# avr_saber_mini.net
KiCad netlist of a schematic drawn in EAGLE
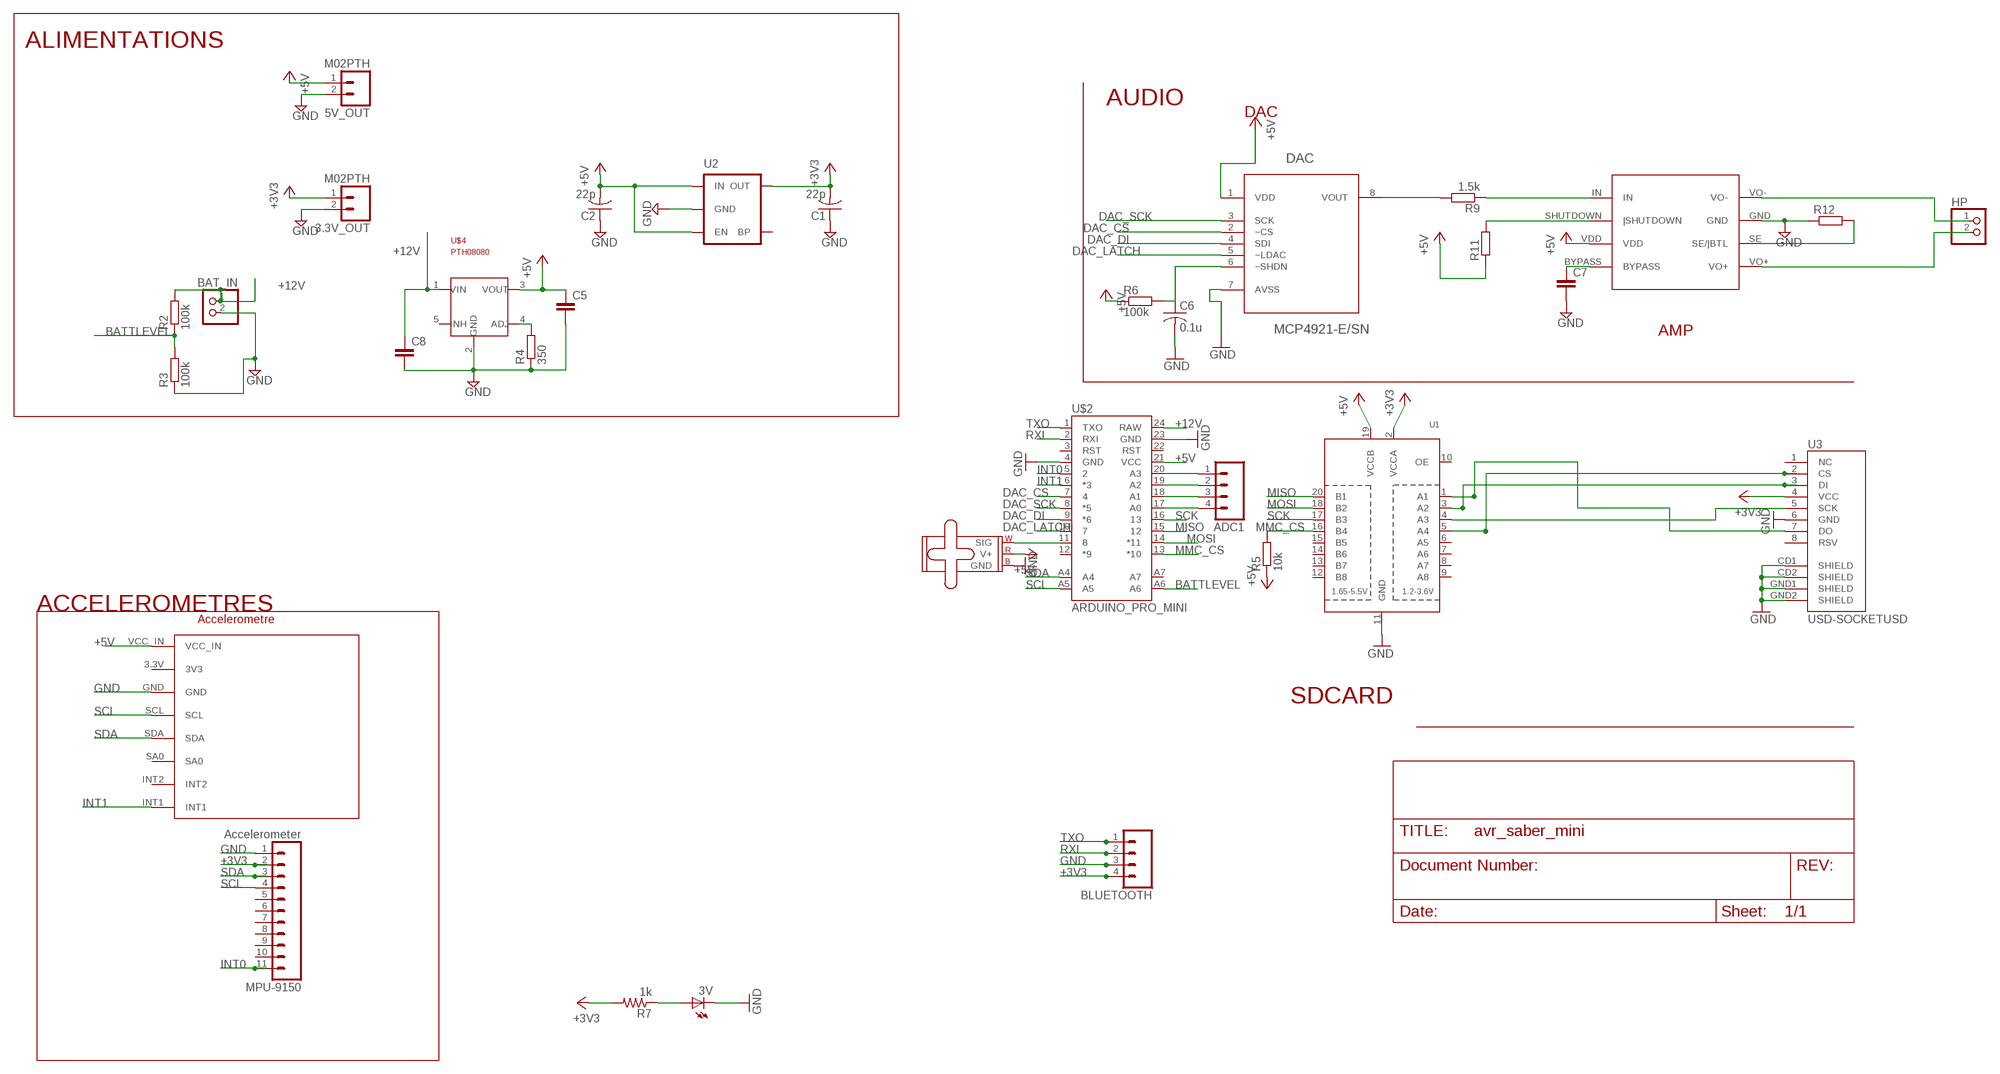
[diagram p0: schematic, sheet 1]

(export (version "E")
  (design (tool "Eeschema 10.0.6"))
  (components
    (comp (ref "3.3V_OUT")
      (value "M02PTH")
      (footprint "eagle-import:1X02")
      (libsource (lib "eagle-import") (part "M02PTH"))
    )
    (comp (ref "3V")
      (value "LEDSML0805")
      (footprint "eagle-import:SML0805")
      (libsource (lib "eagle-import") (part "LEDSML0805"))
    )
    (comp (ref "5V_OUT")
      (value "M02PTH")
      (footprint "eagle-import:1X02")
      (libsource (lib "eagle-import") (part "M02PTH"))
    )
    (comp (ref "ADC1")
      (value "M04PTH")
      (footprint "eagle-import:1X04")
      (libsource (lib "eagle-import") (part "M04PTH"))
    )
    (comp (ref "BAT_IN")
      (value "PINHD-1X2")
      (footprint "eagle-import:1X02")
      (libsource (lib "eagle-import") (part "PINHD-1X2"))
    )
    (comp (ref "BLUETOOTH")
      (value "M04PTH")
      (footprint "eagle-import:1X04")
      (libsource (lib "eagle-import") (part "M04PTH"))
    )
    (comp (ref "C1")
      (value "22p")
      (footprint "eagle-import:C0805")
      (libsource (lib "eagle-import") (part "C-USC0805"))
    )
    (comp (ref "C2")
      (value "22p")
      (footprint "eagle-import:C0805")
      (libsource (lib "eagle-import") (part "C-USC0805"))
    )
    (comp (ref "C5")
      (value "C-EUC1206K")
      (footprint "eagle-import:C1206K")
      (libsource (lib "eagle-import") (part "C-EUC1206K"))
    )
    (comp (ref "C6")
      (value "0.1u")
      (footprint "eagle-import:C0805")
      (libsource (lib "eagle-import") (part "C-USC0805"))
    )
    (comp (ref "C7")
      (value "C-EU025-025X050")
      (footprint "eagle-import:C025-025X050")
      (libsource (lib "eagle-import") (part "C-EU025-025X050"))
    )
    (comp (ref "C8")
      (value "C-EUC1206K")
      (footprint "eagle-import:C1206K")
      (libsource (lib "eagle-import") (part "C-EUC1206K"))
    )
    (comp (ref "DAC")
      (value "MCP4921-E/SN")
      (footprint "eagle-import:SOIC8-N_MC")
      (libsource (lib "eagle-import") (part "MCP4921-E/SN"))
    )
    (comp (ref "HP")
      (value "PINHD-1X2")
      (footprint "eagle-import:1X02")
      (libsource (lib "eagle-import") (part "PINHD-1X2"))
    )
    (comp (ref "LED1")
      (value "SMALL_SERVO")
      (footprint "eagle-import:1X03")
      (libsource (lib "eagle-import") (part "SMALL_SERVO"))
    )
    (comp (ref "MMA8451")
      (value "DEV")
      (footprint "eagle-import:MMA8451")
      (libsource (lib "eagle-import") (part "DEV"))
    )
    (comp (ref "MPU-9150")
      (value "Accelerometer")
      (footprint "eagle-import:1X11")
      (libsource (lib "eagle-import") (part "M11PTH"))
    )
    (comp (ref "R2")
      (value "100k")
      (footprint "eagle-import:R0805")
      (libsource (lib "eagle-import") (part "R-EU_R0805"))
    )
    (comp (ref "R3")
      (value "100k")
      (footprint "eagle-import:R0805")
      (libsource (lib "eagle-import") (part "R-EU_R0805"))
    )
    (comp (ref "R4")
      (value "350")
      (footprint "eagle-import:R0805")
      (libsource (lib "eagle-import") (part "R-EU_R0805"))
    )
    (comp (ref "R5")
      (value "10k")
      (footprint "eagle-import:R0805")
      (libsource (lib "eagle-import") (part "R-EU_R0805"))
    )
    (comp (ref "R6")
      (value "100k")
      (footprint "eagle-import:R0805")
      (libsource (lib "eagle-import") (part "R-EU_R0805"))
    )
    (comp (ref "R7")
      (value "1k")
      (footprint "eagle-import:M0805")
      (libsource (lib "eagle-import") (part "R-US_M0805"))
    )
    (comp (ref "R9")
      (value "1.5k")
      (footprint "eagle-import:R0805")
      (libsource (lib "eagle-import") (part "R-EU_R0805"))
    )
    (comp (ref "R11")
      (value "R-EU_R0805")
      (footprint "eagle-import:R0805")
      (libsource (lib "eagle-import") (part "R-EU_R0805"))
    )
    (comp (ref "R12")
      (value "R-EU_R0805")
      (footprint "eagle-import:R0805")
      (libsource (lib "eagle-import") (part "R-EU_R0805"))
    )
    (comp (ref "U$1")
      (value "TPA0211")
      (footprint "eagle-import:TPA0211")
      (libsource (lib "eagle-import") (part "TPA0211"))
    )
    (comp (ref "U$2")
      (value "ARDUINO_PRO_MINI")
      (footprint "eagle-import:ARDUINO_PRO_MINI")
      (libsource (lib "eagle-import") (part "ARDUINO_PRO_MINI"))
    )
    (comp (ref "U$4")
      (value "PTH08080")
      (footprint "eagle-import:PTH08080EUF")
      (libsource (lib "eagle-import") (part "PTH08080"))
    )
    (comp (ref "U1")
      (value "TXB0108PWR")
      (footprint "eagle-import:TSSOP20")
      (libsource (lib "eagle-import") (part "TXB0108PWR"))
    )
    (comp (ref "U2")
      (value "MIC52053.3V")
      (footprint "eagle-import:SOT23-5")
      (libsource (lib "eagle-import") (part "MIC52053.3V"))
    )
    (comp (ref "U3")
      (value "USD-SOCKETUSD")
      (footprint "eagle-import:USD-SOCKET-PP")
      (libsource (lib "eagle-import") (part "USD-SOCKETUSD"))
    )
  )
  (nets
    (net (code "1") (name "+3V3") (class "Default")
      (node (ref "3.3V_OUT") (pin "1") (pinfunction "1_1") (pintype "passive"))
      (node (ref "BLUETOOTH") (pin "4") (pinfunction "4_4") (pintype "passive"))
      (node (ref "C1") (pin "2") (pinfunction "2_2") (pintype "passive"))
      (node (ref "MPU-9150") (pin "2") (pinfunction "2_2") (pintype "passive"))
      (node (ref "R7") (pin "2") (pinfunction "2_2") (pintype "passive"))
      (node (ref "U1") (pin "2") (pinfunction "VCCA_2") (pintype "bidirectional"))
      (node (ref "U2") (pin "5") (pinfunction "OUT_5") (pintype "passive"))
      (node (ref "U3") (pin "4") (pinfunction "VCC_4") (pintype "bidirectional"))
    )
    (net (code "2") (name "+5V") (class "Default")
      (node (ref "5V_OUT") (pin "1") (pinfunction "1_1") (pintype "passive"))
      (node (ref "C2") (pin "2") (pinfunction "2_2") (pintype "passive"))
      (node (ref "C5") (pin "1") (pinfunction "1_1") (pintype "passive"))
      (node (ref "DAC") (pin "1") (pinfunction "VDD_1") (pintype "power_in"))
      (node (ref "LED1") (pin "2") (pinfunction "V+_2") (pintype "bidirectional"))
      (node (ref "MMA8451") (pin "VCC_IN") (pinfunction "VCC_IN_VCC_IN") (pintype "bidirectional"))
      (node (ref "R11") (pin "1") (pinfunction "1_1") (pintype "passive"))
      (node (ref "R5") (pin "1") (pinfunction "1_1") (pintype "passive"))
      (node (ref "R6") (pin "1") (pinfunction "1_1") (pintype "passive"))
      (node (ref "U$1") (pin "VDD") (pinfunction "VDD_VDD") (pintype "bidirectional"))
      (node (ref "U$2") (pin "21") (pinfunction "VCC_21") (pintype "bidirectional"))
      (node (ref "U$4") (pin "3") (pinfunction "VOUT_3") (pintype "power_in"))
      (node (ref "U1") (pin "19") (pinfunction "VCCB_19") (pintype "bidirectional"))
      (node (ref "U2") (pin "1") (pinfunction "IN_1") (pintype "input"))
      (node (ref "U2") (pin "3") (pinfunction "EN_3") (pintype "input"))
    )
    (net (code "3") (name "/+12V") (class "Default")
      (node (ref "BAT_IN") (pin "1") (pinfunction "1_1") (pintype "passive"))
      (node (ref "C8") (pin "1") (pinfunction "1_1") (pintype "passive"))
      (node (ref "R2") (pin "2") (pinfunction "2_2") (pintype "passive"))
      (node (ref "U$2") (pin "24") (pinfunction "RAW_24") (pintype "bidirectional"))
      (node (ref "U$4") (pin "1") (pinfunction "VIN_1") (pintype "power_in"))
    )
    (net (code "4") (name "/BATTLEVEL") (class "Default")
      (node (ref "R2") (pin "1") (pinfunction "1_1") (pintype "passive"))
      (node (ref "R3") (pin "2") (pinfunction "2_2") (pintype "passive"))
      (node (ref "U$2") (pin "A6") (pinfunction "A6_A6") (pintype "bidirectional"))
    )
    (net (code "5") (name "/DAC_CS") (class "Default")
      (node (ref "DAC") (pin "2") (pinfunction "~{CS}_2") (pintype "input"))
      (node (ref "U$2") (pin "7") (pinfunction "4_7") (pintype "bidirectional"))
    )
    (net (code "6") (name "/DAC_DI") (class "Default")
      (node (ref "DAC") (pin "4") (pinfunction "SDI_4") (pintype "input"))
      (node (ref "U$2") (pin "9") (pinfunction "*6_9") (pintype "bidirectional"))
    )
    (net (code "7") (name "/DAC_LATCH") (class "Default")
      (node (ref "DAC") (pin "5") (pinfunction "~{LDAC}_5") (pintype "input"))
      (node (ref "U$2") (pin "10") (pinfunction "7_10") (pintype "bidirectional"))
    )
    (net (code "8") (name "/DAC_SCK") (class "Default")
      (node (ref "DAC") (pin "3") (pinfunction "SCK_3") (pintype "input"))
      (node (ref "U$2") (pin "8") (pinfunction "*5_8") (pintype "bidirectional"))
    )
    (net (code "9") (name "/INT0") (class "Default")
      (node (ref "MPU-9150") (pin "11") (pinfunction "11_11") (pintype "passive"))
      (node (ref "U$2") (pin "5") (pinfunction "2_5") (pintype "bidirectional"))
    )
    (net (code "10") (name "/INT1") (class "Default")
      (node (ref "MMA8451") (pin "INT1") (pinfunction "INT1_INT1") (pintype "bidirectional"))
      (node (ref "U$2") (pin "6") (pinfunction "*3_6") (pintype "bidirectional"))
    )
    (net (code "11") (name "/MISO") (class "Default")
      (node (ref "U$2") (pin "15") (pinfunction "12_15") (pintype "bidirectional"))
      (node (ref "U1") (pin "20") (pinfunction "B1_20") (pintype "bidirectional"))
    )
    (net (code "12") (name "/MMC_CS") (class "Default")
      (node (ref "R5") (pin "2") (pinfunction "2_2") (pintype "passive"))
      (node (ref "U$2") (pin "13") (pinfunction "*10_13") (pintype "bidirectional"))
      (node (ref "U1") (pin "16") (pinfunction "B4_16") (pintype "bidirectional"))
    )
    (net (code "13") (name "/MOSI") (class "Default")
      (node (ref "U$2") (pin "14") (pinfunction "*11_14") (pintype "bidirectional"))
      (node (ref "U1") (pin "18") (pinfunction "B2_18") (pintype "bidirectional"))
    )
    (net (code "14") (name "/RXI") (class "Default")
      (node (ref "BLUETOOTH") (pin "2") (pinfunction "2_2") (pintype "passive"))
      (node (ref "U$2") (pin "2") (pinfunction "RXI_2") (pintype "bidirectional"))
    )
    (net (code "15") (name "/SCK") (class "Default")
      (node (ref "U$2") (pin "16") (pinfunction "13_16") (pintype "bidirectional"))
      (node (ref "U1") (pin "17") (pinfunction "B3_17") (pintype "bidirectional"))
    )
    (net (code "16") (name "/SCL") (class "Default")
      (node (ref "MMA8451") (pin "SCL") (pinfunction "SCL_SCL") (pintype "bidirectional"))
      (node (ref "MPU-9150") (pin "4") (pinfunction "4_4") (pintype "passive"))
      (node (ref "U$2") (pin "A5") (pinfunction "A5_A5") (pintype "bidirectional"))
    )
    (net (code "17") (name "/SDA") (class "Default")
      (node (ref "MMA8451") (pin "SDA") (pinfunction "SDA_SDA") (pintype "bidirectional"))
      (node (ref "MPU-9150") (pin "3") (pinfunction "3_3") (pintype "passive"))
      (node (ref "U$2") (pin "A4") (pinfunction "A4_A4") (pintype "bidirectional"))
    )
    (net (code "18") (name "/TXO") (class "Default")
      (node (ref "BLUETOOTH") (pin "1") (pinfunction "1_1") (pintype "passive"))
      (node (ref "U$2") (pin "1") (pinfunction "TXO_1") (pintype "bidirectional"))
    )
    (net (code "19") (name "GND") (class "Default")
      (node (ref "3.3V_OUT") (pin "2") (pinfunction "2_2") (pintype "passive"))
      (node (ref "3V") (pin "C") (pinfunction "C_C") (pintype "passive"))
      (node (ref "5V_OUT") (pin "2") (pinfunction "2_2") (pintype "passive"))
      (node (ref "BAT_IN") (pin "2") (pinfunction "2_2") (pintype "passive"))
      (node (ref "BLUETOOTH") (pin "3") (pinfunction "3_3") (pintype "passive"))
      (node (ref "C1") (pin "1") (pinfunction "1_1") (pintype "passive"))
      (node (ref "C2") (pin "1") (pinfunction "1_1") (pintype "passive"))
      (node (ref "C5") (pin "2") (pinfunction "2_2") (pintype "passive"))
      (node (ref "C6") (pin "2") (pinfunction "2_2") (pintype "passive"))
      (node (ref "C7") (pin "2") (pinfunction "2_2") (pintype "passive"))
      (node (ref "C8") (pin "2") (pinfunction "2_2") (pintype "passive"))
      (node (ref "DAC") (pin "7") (pinfunction "AVSS_7") (pintype "power_in"))
      (node (ref "LED1") (pin "3") (pinfunction "GND_3") (pintype "bidirectional"))
      (node (ref "MMA8451") (pin "GND") (pinfunction "GND_GND") (pintype "bidirectional"))
      (node (ref "MPU-9150") (pin "1") (pinfunction "1_1") (pintype "passive"))
      (node (ref "R12") (pin "1") (pinfunction "1_1") (pintype "passive"))
      (node (ref "R3") (pin "1") (pinfunction "1_1") (pintype "passive"))
      (node (ref "R4") (pin "1") (pinfunction "1_1") (pintype "passive"))
      (node (ref "U$1") (pin "GND") (pinfunction "GND_GND") (pintype "bidirectional"))
      (node (ref "U$2") (pin "23") (pinfunction "GND_23") (pintype "bidirectional"))
      (node (ref "U$2") (pin "4") (pinfunction "GND_4") (pintype "bidirectional"))
      (node (ref "U$4") (pin "2") (pinfunction "GND_2") (pintype "power_in"))
      (node (ref "U1") (pin "11") (pinfunction "GND_11") (pintype "bidirectional"))
      (node (ref "U2") (pin "2") (pinfunction "GND_2") (pintype "input"))
      (node (ref "U3") (pin "6") (pinfunction "GND_6") (pintype "bidirectional"))
      (node (ref "U3") (pin "CD1") (pinfunction "SHIELD_CD1") (pintype "bidirectional"))
      (node (ref "U3") (pin "CD2") (pinfunction "SHIELD_CD2") (pintype "bidirectional"))
      (node (ref "U3") (pin "GND1") (pinfunction "SHIELD_GND1") (pintype "bidirectional"))
      (node (ref "U3") (pin "GND2") (pinfunction "SHIELD_GND2") (pintype "bidirectional"))
    )
    (net (code "20") (name "Net-(3V-PadA)") (class "Default")
      (node (ref "3V") (pin "A") (pinfunction "A_A") (pintype "passive"))
      (node (ref "R7") (pin "1") (pinfunction "1_1") (pintype "passive"))
    )
    (net (code "21") (name "Net-(C7-Pad1)") (class "Default")
      (node (ref "C7") (pin "1") (pinfunction "1_1") (pintype "passive"))
      (node (ref "U$1") (pin "BYPASS") (pinfunction "BYPASS_BYPASS") (pintype "bidirectional"))
    )
    (net (code "22") (name "Net-(DAC-VOUT)") (class "Default")
      (node (ref "DAC") (pin "8") (pinfunction "VOUT_8") (pintype "output"))
      (node (ref "R9") (pin "2") (pinfunction "2_2") (pintype "passive"))
    )
    (net (code "23") (name "Net-(DAC-~{SHDN})") (class "Default")
      (node (ref "C6") (pin "1") (pinfunction "1_1") (pintype "passive"))
      (node (ref "DAC") (pin "6") (pinfunction "~{SHDN}_6") (pintype "input"))
      (node (ref "R6") (pin "2") (pinfunction "2_2") (pintype "passive"))
    )
    (net (code "24") (name "Net-(HP-Pad1)") (class "Default")
      (node (ref "HP") (pin "1") (pinfunction "1_1") (pintype "passive"))
      (node (ref "U$1") (pin "VO-") (pinfunction "VO-_VO-") (pintype "bidirectional"))
    )
    (net (code "25") (name "Net-(HP-Pad2)") (class "Default")
      (node (ref "HP") (pin "2") (pinfunction "2_2") (pintype "passive"))
      (node (ref "U$1") (pin "VO+") (pinfunction "VO+_VO+") (pintype "bidirectional"))
    )
    (net (code "26") (name "Net-(LED1-SIG)") (class "Default")
      (node (ref "LED1") (pin "1") (pinfunction "SIG_1") (pintype "bidirectional"))
      (node (ref "U$2") (pin "11") (pinfunction "8_11") (pintype "bidirectional"))
    )
    (net (code "27") (name "Net-(R9-Pad1)") (class "Default")
      (node (ref "R9") (pin "1") (pinfunction "1_1") (pintype "passive"))
      (node (ref "U$1") (pin "IN") (pinfunction "IN_IN") (pintype "bidirectional"))
    )
    (net (code "28") (name "Net-(U$1-SE{slash}|BTL)") (class "Default")
      (node (ref "R12") (pin "2") (pinfunction "2_2") (pintype "passive"))
      (node (ref "U$1") (pin "SE") (pinfunction "SE/|BTL_SE") (pintype "bidirectional"))
    )
    (net (code "29") (name "Net-(U$1-|SHUTDOWN)") (class "Default")
      (node (ref "R11") (pin "2") (pinfunction "2_2") (pintype "passive"))
      (node (ref "U$1") (pin "SHUTDOWN") (pinfunction "|SHUTDOWN_SHUTDOWN") (pintype "bidirectional"))
    )
    (net (code "30") (name "Net-(U$2-A0)") (class "Default")
      (node (ref "ADC1") (pin "4") (pinfunction "4_4") (pintype "passive"))
      (node (ref "U$2") (pin "17") (pinfunction "A0_17") (pintype "bidirectional"))
    )
    (net (code "31") (name "Net-(U$2-A1)") (class "Default")
      (node (ref "ADC1") (pin "3") (pinfunction "3_3") (pintype "passive"))
      (node (ref "U$2") (pin "18") (pinfunction "A1_18") (pintype "bidirectional"))
    )
    (net (code "32") (name "Net-(U$2-A2)") (class "Default")
      (node (ref "ADC1") (pin "2") (pinfunction "2_2") (pintype "passive"))
      (node (ref "U$2") (pin "19") (pinfunction "A2_19") (pintype "bidirectional"))
    )
    (net (code "33") (name "Net-(U$2-A3)") (class "Default")
      (node (ref "ADC1") (pin "1") (pinfunction "1_1") (pintype "passive"))
      (node (ref "U$2") (pin "20") (pinfunction "A3_20") (pintype "bidirectional"))
    )
    (net (code "34") (name "Net-(U$4-ADJ)") (class "Default")
      (node (ref "R4") (pin "2") (pinfunction "2_2") (pintype "passive"))
      (node (ref "U$4") (pin "4") (pinfunction "ADJ_4") (pintype "passive"))
    )
    (net (code "35") (name "Net-(U1-A1)") (class "Default")
      (node (ref "U1") (pin "1") (pinfunction "A1_1") (pintype "bidirectional"))
      (node (ref "U3") (pin "7") (pinfunction "DO_7") (pintype "bidirectional"))
    )
    (net (code "36") (name "Net-(U1-A2)") (class "Default")
      (node (ref "U1") (pin "3") (pinfunction "A2_3") (pintype "bidirectional"))
      (node (ref "U3") (pin "3") (pinfunction "DI_3") (pintype "bidirectional"))
    )
    (net (code "37") (name "Net-(U1-A3)") (class "Default")
      (node (ref "U1") (pin "4") (pinfunction "A3_4") (pintype "bidirectional"))
      (node (ref "U3") (pin "5") (pinfunction "SCK_5") (pintype "bidirectional"))
    )
    (net (code "38") (name "Net-(U1-A4)") (class "Default")
      (node (ref "U1") (pin "5") (pinfunction "A4_5") (pintype "bidirectional"))
      (node (ref "U3") (pin "2") (pinfunction "CS_2") (pintype "bidirectional"))
    )
    (net (code "39") (name "unconnected-(MMA8451-3V3-Pad3.3V)") (class "Default")
      (node (ref "MMA8451") (pin "3.3V") (pinfunction "3V3_3.3V") (pintype "bidirectional"))
    )
    (net (code "40") (name "unconnected-(MMA8451-PadINT2)") (class "Default")
      (node (ref "MMA8451") (pin "INT2") (pinfunction "INT2_INT2") (pintype "bidirectional"))
    )
    (net (code "41") (name "unconnected-(MMA8451-PadSA0)") (class "Default")
      (node (ref "MMA8451") (pin "SA0") (pinfunction "SA0_SA0") (pintype "bidirectional"))
    )
    (net (code "42") (name "unconnected-(MPU-9150-Pad5)") (class "Default")
      (node (ref "MPU-9150") (pin "5") (pinfunction "5_5") (pintype "passive"))
    )
    (net (code "43") (name "unconnected-(MPU-9150-Pad6)") (class "Default")
      (node (ref "MPU-9150") (pin "6") (pinfunction "6_6") (pintype "passive"))
    )
    (net (code "44") (name "unconnected-(MPU-9150-Pad7)") (class "Default")
      (node (ref "MPU-9150") (pin "7") (pinfunction "7_7") (pintype "passive"))
    )
    (net (code "45") (name "unconnected-(MPU-9150-Pad8)") (class "Default")
      (node (ref "MPU-9150") (pin "8") (pinfunction "8_8") (pintype "passive"))
    )
    (net (code "46") (name "unconnected-(MPU-9150-Pad9)") (class "Default")
      (node (ref "MPU-9150") (pin "9") (pinfunction "9_9") (pintype "passive"))
    )
    (net (code "47") (name "unconnected-(MPU-9150-Pad10)") (class "Default")
      (node (ref "MPU-9150") (pin "10") (pinfunction "10_10") (pintype "passive"))
    )
    (net (code "48") (name "unconnected-(U$2-*9-Pad12)") (class "Default")
      (node (ref "U$2") (pin "12") (pinfunction "*9_12") (pintype "bidirectional"))
    )
    (net (code "49") (name "unconnected-(U$2-PadA7)") (class "Default")
      (node (ref "U$2") (pin "A7") (pinfunction "A7_A7") (pintype "bidirectional"))
    )
    (net (code "50") (name "unconnected-(U$2-RST-Pad3)") (class "Default")
      (node (ref "U$2") (pin "3") (pinfunction "RST_3") (pintype "bidirectional"))
    )
    (net (code "51") (name "unconnected-(U$2-RST-Pad22)") (class "Default")
      (node (ref "U$2") (pin "22") (pinfunction "RST_22") (pintype "bidirectional"))
    )
    (net (code "52") (name "unconnected-(U$4-INH-Pad5)") (class "Default")
      (node (ref "U$4") (pin "5") (pinfunction "INH_5") (pintype "bidirectional"))
    )
    (net (code "53") (name "unconnected-(U1-A5-Pad6)") (class "Default")
      (node (ref "U1") (pin "6") (pinfunction "A5_6") (pintype "bidirectional"))
    )
    (net (code "54") (name "unconnected-(U1-A6-Pad7)") (class "Default")
      (node (ref "U1") (pin "7") (pinfunction "A6_7") (pintype "bidirectional"))
    )
    (net (code "55") (name "unconnected-(U1-A7-Pad8)") (class "Default")
      (node (ref "U1") (pin "8") (pinfunction "A7_8") (pintype "bidirectional"))
    )
    (net (code "56") (name "unconnected-(U1-A8-Pad9)") (class "Default")
      (node (ref "U1") (pin "9") (pinfunction "A8_9") (pintype "bidirectional"))
    )
    (net (code "57") (name "unconnected-(U1-B5-Pad15)") (class "Default")
      (node (ref "U1") (pin "15") (pinfunction "B5_15") (pintype "bidirectional"))
    )
    (net (code "58") (name "unconnected-(U1-B6-Pad14)") (class "Default")
      (node (ref "U1") (pin "14") (pinfunction "B6_14") (pintype "bidirectional"))
    )
    (net (code "59") (name "unconnected-(U1-B7-Pad13)") (class "Default")
      (node (ref "U1") (pin "13") (pinfunction "B7_13") (pintype "bidirectional"))
    )
    (net (code "60") (name "unconnected-(U1-B8-Pad12)") (class "Default")
      (node (ref "U1") (pin "12") (pinfunction "B8_12") (pintype "bidirectional"))
    )
    (net (code "61") (name "unconnected-(U1-OE-Pad10)") (class "Default")
      (node (ref "U1") (pin "10") (pinfunction "OE_10") (pintype "bidirectional"))
    )
    (net (code "62") (name "unconnected-(U2-BP-Pad4)") (class "Default")
      (node (ref "U2") (pin "4") (pinfunction "BP_4") (pintype "input"))
    )
    (net (code "63") (name "unconnected-(U3-NC-Pad1)") (class "Default")
      (node (ref "U3") (pin "1") (pinfunction "NC_1") (pintype "bidirectional"))
    )
    (net (code "64") (name "unconnected-(U3-RSV-Pad8)") (class "Default")
      (node (ref "U3") (pin "8") (pinfunction "RSV_8") (pintype "bidirectional"))
    )
  )
)
